# SrcBackplaneSingleLayer00_01.net
KiCad netlist of a schematic drawn in EAGLE
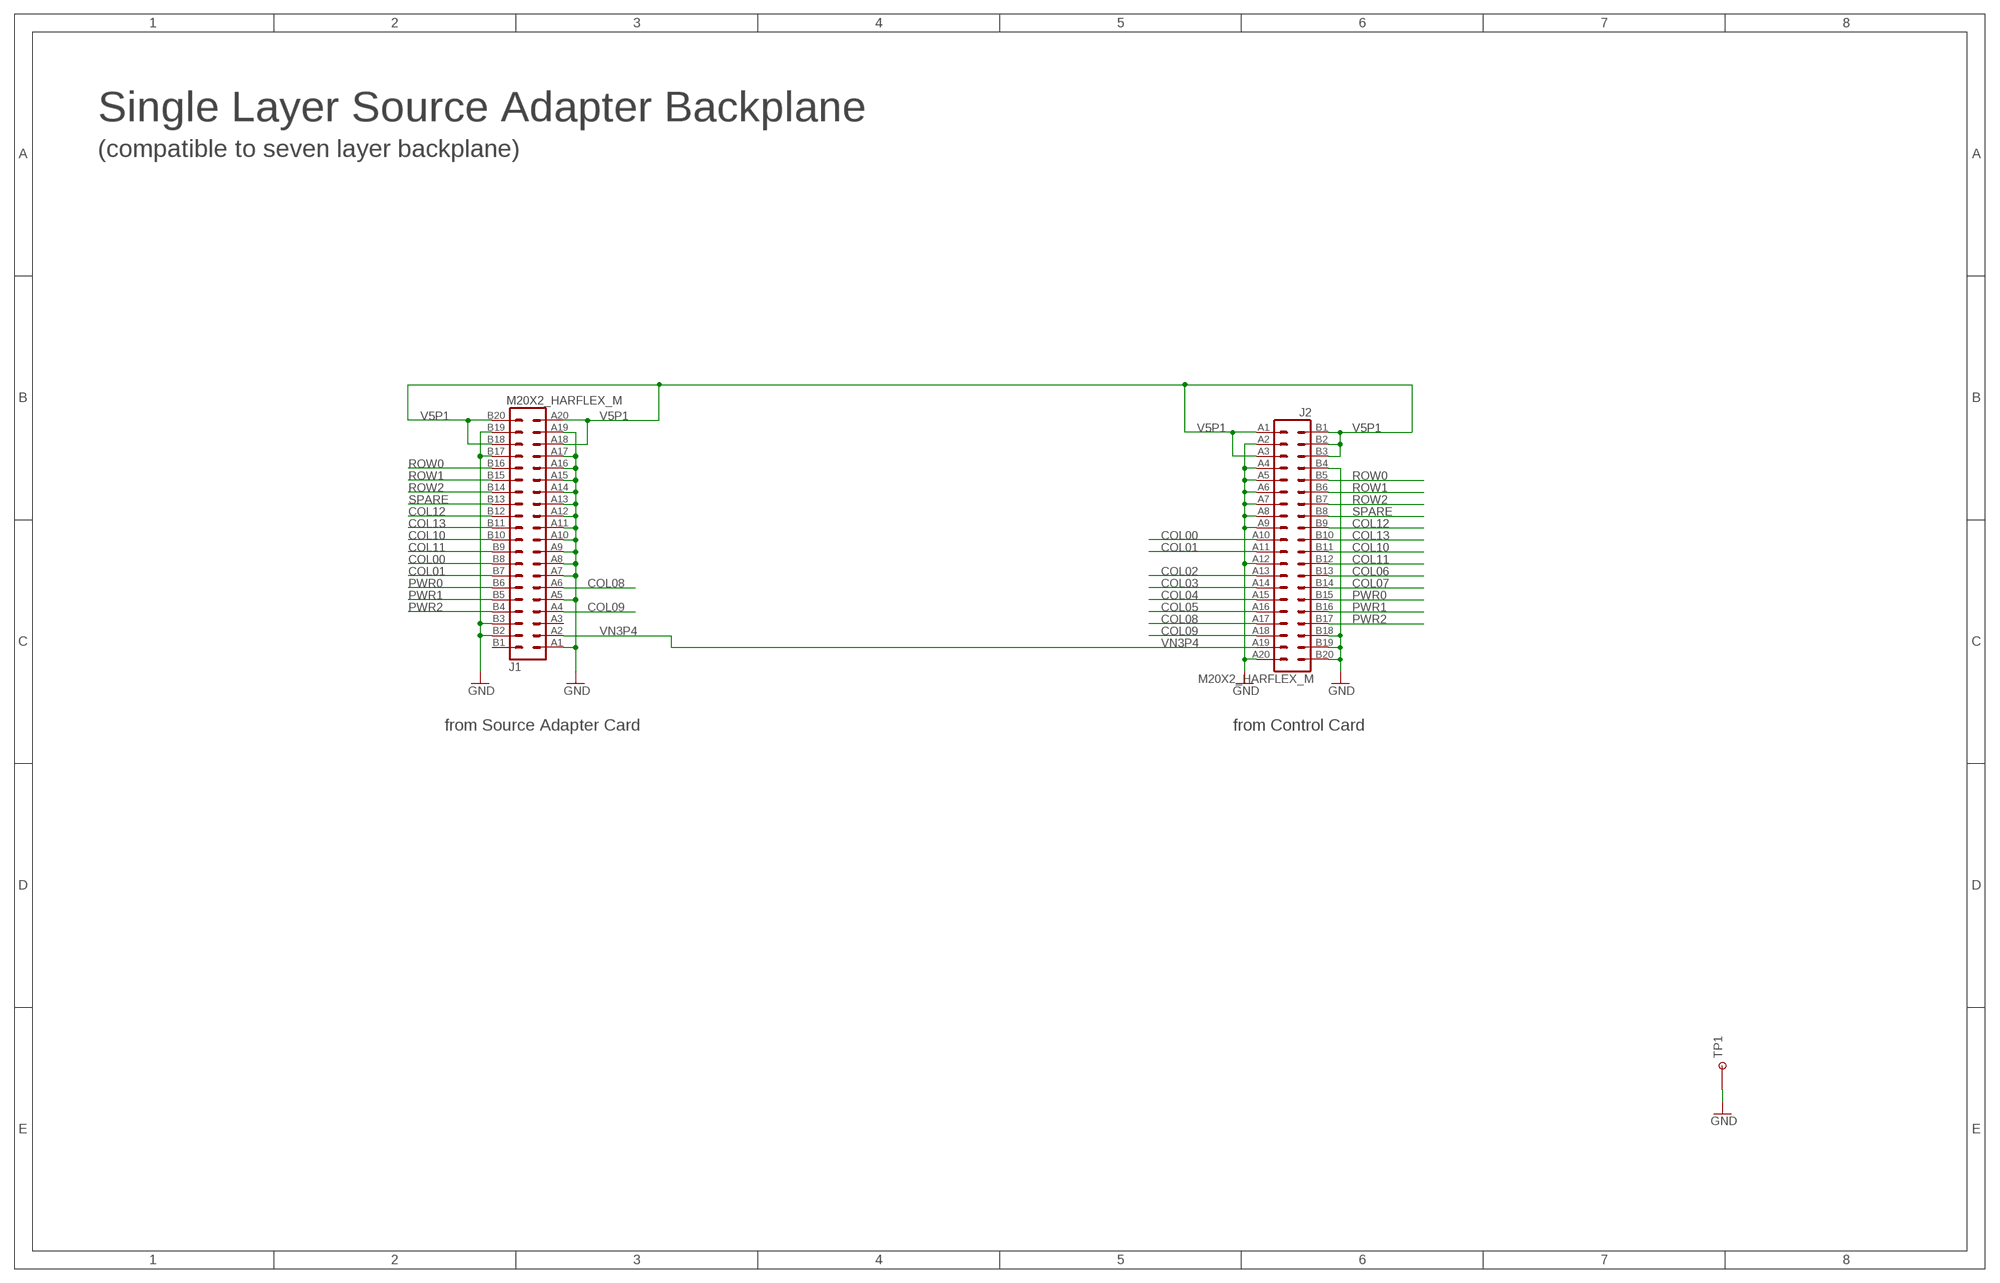
[diagram p0: schematic, sheet 1]

(export (version "E")
  (design (tool "Eeschema 10.0.6"))
  (components
    (comp (ref "J1")
      (value "M20X2_HARFLEX_M")
      (footprint "eagle-import:M20X2_HARFLEX_M")
      (libsource (lib "eagle-import") (part "M20X2_HARFLEX_M"))
    )
    (comp (ref "J2")
      (value "M20X2_HARFLEX_M")
      (footprint "eagle-import:M20X2_HARFLEX_M")
      (libsource (lib "eagle-import") (part "M20X2_HARFLEX_M"))
    )
    (comp (ref "TP1")
      (value "TESTPOINT_ROUND")
      (footprint "eagle-import:TESTPAD_ROUND")
      (libsource (lib "eagle-import") (part "TESTPOINT_ROUND"))
    )
  )
  (nets
    (net (code "1") (name "/COL00") (class "Default")
      (node (ref "J1") (pin "B8") (pinfunction "15_B8") (pintype "passive"))
      (node (ref "J2") (pin "A10") (pinfunction "20_A10") (pintype "passive"))
    )
    (net (code "2") (name "/COL01") (class "Default")
      (node (ref "J1") (pin "B7") (pinfunction "13_B7") (pintype "passive"))
      (node (ref "J2") (pin "A11") (pinfunction "22_A11") (pintype "passive"))
    )
    (net (code "3") (name "/COL02") (class "Default")
      (node (ref "J2") (pin "A13") (pinfunction "26_A13") (pintype "passive"))
    )
    (net (code "4") (name "/COL03") (class "Default")
      (node (ref "J2") (pin "A14") (pinfunction "28_A14") (pintype "passive"))
    )
    (net (code "5") (name "/COL04") (class "Default")
      (node (ref "J2") (pin "A15") (pinfunction "30_A15") (pintype "passive"))
    )
    (net (code "6") (name "/COL05") (class "Default")
      (node (ref "J2") (pin "A16") (pinfunction "32_A16") (pintype "passive"))
    )
    (net (code "7") (name "/COL06") (class "Default")
      (node (ref "J2") (pin "B13") (pinfunction "25_B13") (pintype "passive"))
    )
    (net (code "8") (name "/COL07") (class "Default")
      (node (ref "J2") (pin "B14") (pinfunction "27_B14") (pintype "passive"))
    )
    (net (code "9") (name "/COL08") (class "Default")
      (node (ref "J1") (pin "A6") (pinfunction "12_A6") (pintype "passive"))
      (node (ref "J2") (pin "A17") (pinfunction "34_A17") (pintype "passive"))
    )
    (net (code "10") (name "/COL09") (class "Default")
      (node (ref "J1") (pin "A4") (pinfunction "8_A4") (pintype "passive"))
      (node (ref "J2") (pin "A18") (pinfunction "36_A18") (pintype "passive"))
    )
    (net (code "11") (name "/COL10") (class "Default")
      (node (ref "J1") (pin "B10") (pinfunction "19_B10") (pintype "passive"))
      (node (ref "J2") (pin "B11") (pinfunction "21_B11") (pintype "passive"))
    )
    (net (code "12") (name "/COL11") (class "Default")
      (node (ref "J1") (pin "B9") (pinfunction "17_B9") (pintype "passive"))
      (node (ref "J2") (pin "B12") (pinfunction "23_B12") (pintype "passive"))
    )
    (net (code "13") (name "/COL12") (class "Default")
      (node (ref "J1") (pin "B12") (pinfunction "23_B12") (pintype "passive"))
      (node (ref "J2") (pin "B9") (pinfunction "17_B9") (pintype "passive"))
    )
    (net (code "14") (name "/COL13") (class "Default")
      (node (ref "J1") (pin "B11") (pinfunction "21_B11") (pintype "passive"))
      (node (ref "J2") (pin "B10") (pinfunction "19_B10") (pintype "passive"))
    )
    (net (code "15") (name "/PWR0") (class "Default")
      (node (ref "J1") (pin "B6") (pinfunction "11_B6") (pintype "passive"))
      (node (ref "J2") (pin "B15") (pinfunction "29_B15") (pintype "passive"))
    )
    (net (code "16") (name "/PWR1") (class "Default")
      (node (ref "J1") (pin "B5") (pinfunction "9_B5") (pintype "passive"))
      (node (ref "J2") (pin "B16") (pinfunction "31_B16") (pintype "passive"))
    )
    (net (code "17") (name "/PWR2") (class "Default")
      (node (ref "J1") (pin "B4") (pinfunction "7_B4") (pintype "passive"))
      (node (ref "J2") (pin "B17") (pinfunction "33_B17") (pintype "passive"))
    )
    (net (code "18") (name "/ROW0") (class "Default")
      (node (ref "J1") (pin "B16") (pinfunction "31_B16") (pintype "passive"))
      (node (ref "J2") (pin "B5") (pinfunction "9_B5") (pintype "passive"))
    )
    (net (code "19") (name "/ROW1") (class "Default")
      (node (ref "J1") (pin "B15") (pinfunction "29_B15") (pintype "passive"))
      (node (ref "J2") (pin "B6") (pinfunction "11_B6") (pintype "passive"))
    )
    (net (code "20") (name "/ROW2") (class "Default")
      (node (ref "J1") (pin "B14") (pinfunction "27_B14") (pintype "passive"))
      (node (ref "J2") (pin "B7") (pinfunction "13_B7") (pintype "passive"))
    )
    (net (code "21") (name "/SPARE") (class "Default")
      (node (ref "J1") (pin "B13") (pinfunction "25_B13") (pintype "passive"))
      (node (ref "J2") (pin "B8") (pinfunction "15_B8") (pintype "passive"))
    )
    (net (code "22") (name "/V5P1") (class "Default")
      (node (ref "J1") (pin "A18") (pinfunction "36_A18") (pintype "passive"))
      (node (ref "J1") (pin "A20") (pinfunction "40_A20") (pintype "passive"))
      (node (ref "J1") (pin "B18") (pinfunction "35_B18") (pintype "passive"))
      (node (ref "J1") (pin "B20") (pinfunction "39_B20") (pintype "passive"))
      (node (ref "J2") (pin "A1") (pinfunction "2_A1") (pintype "passive"))
      (node (ref "J2") (pin "A3") (pinfunction "6_A3") (pintype "passive"))
      (node (ref "J2") (pin "B1") (pinfunction "1_B1") (pintype "passive"))
      (node (ref "J2") (pin "B2") (pinfunction "3_B2") (pintype "passive"))
      (node (ref "J2") (pin "B3") (pinfunction "5_B3") (pintype "passive"))
    )
    (net (code "23") (name "/VN3P4") (class "Default")
      (node (ref "J1") (pin "A2") (pinfunction "4_A2") (pintype "passive"))
      (node (ref "J2") (pin "A19") (pinfunction "38_A19") (pintype "passive"))
    )
    (net (code "24") (name "GND") (class "Default")
      (node (ref "J1") (pin "A1") (pinfunction "2_A1") (pintype "passive"))
      (node (ref "J1") (pin "A10") (pinfunction "20_A10") (pintype "passive"))
      (node (ref "J1") (pin "A11") (pinfunction "22_A11") (pintype "passive"))
      (node (ref "J1") (pin "A12") (pinfunction "24_A12") (pintype "passive"))
      (node (ref "J1") (pin "A13") (pinfunction "26_A13") (pintype "passive"))
      (node (ref "J1") (pin "A14") (pinfunction "28_A14") (pintype "passive"))
      (node (ref "J1") (pin "A15") (pinfunction "30_A15") (pintype "passive"))
      (node (ref "J1") (pin "A16") (pinfunction "32_A16") (pintype "passive"))
      (node (ref "J1") (pin "A17") (pinfunction "34_A17") (pintype "passive"))
      (node (ref "J1") (pin "A19") (pinfunction "38_A19") (pintype "passive"))
      (node (ref "J1") (pin "A5") (pinfunction "10_A5") (pintype "passive"))
      (node (ref "J1") (pin "A7") (pinfunction "14_A7") (pintype "passive"))
      (node (ref "J1") (pin "A8") (pinfunction "16_A8") (pintype "passive"))
      (node (ref "J1") (pin "A9") (pinfunction "18_A9") (pintype "passive"))
      (node (ref "J1") (pin "B17") (pinfunction "33_B17") (pintype "passive"))
      (node (ref "J1") (pin "B19") (pinfunction "37_B19") (pintype "passive"))
      (node (ref "J1") (pin "B2") (pinfunction "3_B2") (pintype "passive"))
      (node (ref "J1") (pin "B3") (pinfunction "5_B3") (pintype "passive"))
      (node (ref "J2") (pin "A12") (pinfunction "24_A12") (pintype "passive"))
      (node (ref "J2") (pin "A2") (pinfunction "4_A2") (pintype "passive"))
      (node (ref "J2") (pin "A20") (pinfunction "40_A20") (pintype "passive"))
      (node (ref "J2") (pin "A4") (pinfunction "8_A4") (pintype "passive"))
      (node (ref "J2") (pin "A5") (pinfunction "10_A5") (pintype "passive"))
      (node (ref "J2") (pin "A6") (pinfunction "12_A6") (pintype "passive"))
      (node (ref "J2") (pin "A7") (pinfunction "14_A7") (pintype "passive"))
      (node (ref "J2") (pin "A8") (pinfunction "16_A8") (pintype "passive"))
      (node (ref "J2") (pin "A9") (pinfunction "18_A9") (pintype "passive"))
      (node (ref "J2") (pin "B18") (pinfunction "35_B18") (pintype "passive"))
      (node (ref "J2") (pin "B19") (pinfunction "37_B19") (pintype "passive"))
      (node (ref "J2") (pin "B20") (pinfunction "39_B20") (pintype "passive"))
      (node (ref "J2") (pin "B4") (pinfunction "7_B4") (pintype "passive"))
      (node (ref "TP1") (pin "P$1") (pinfunction "P$1_P$1") (pintype "bidirectional"))
    )
    (net (code "25") (name "unconnected-(J1-1-PadB1)") (class "Default")
      (node (ref "J1") (pin "B1") (pinfunction "1_B1") (pintype "passive"))
    )
    (net (code "26") (name "unconnected-(J1-6-PadA3)") (class "Default")
      (node (ref "J1") (pin "A3") (pinfunction "6_A3") (pintype "passive"))
    )
  )
)
